# Sensing.net
KiCad netlist of a schematic drawn in Altium Designer
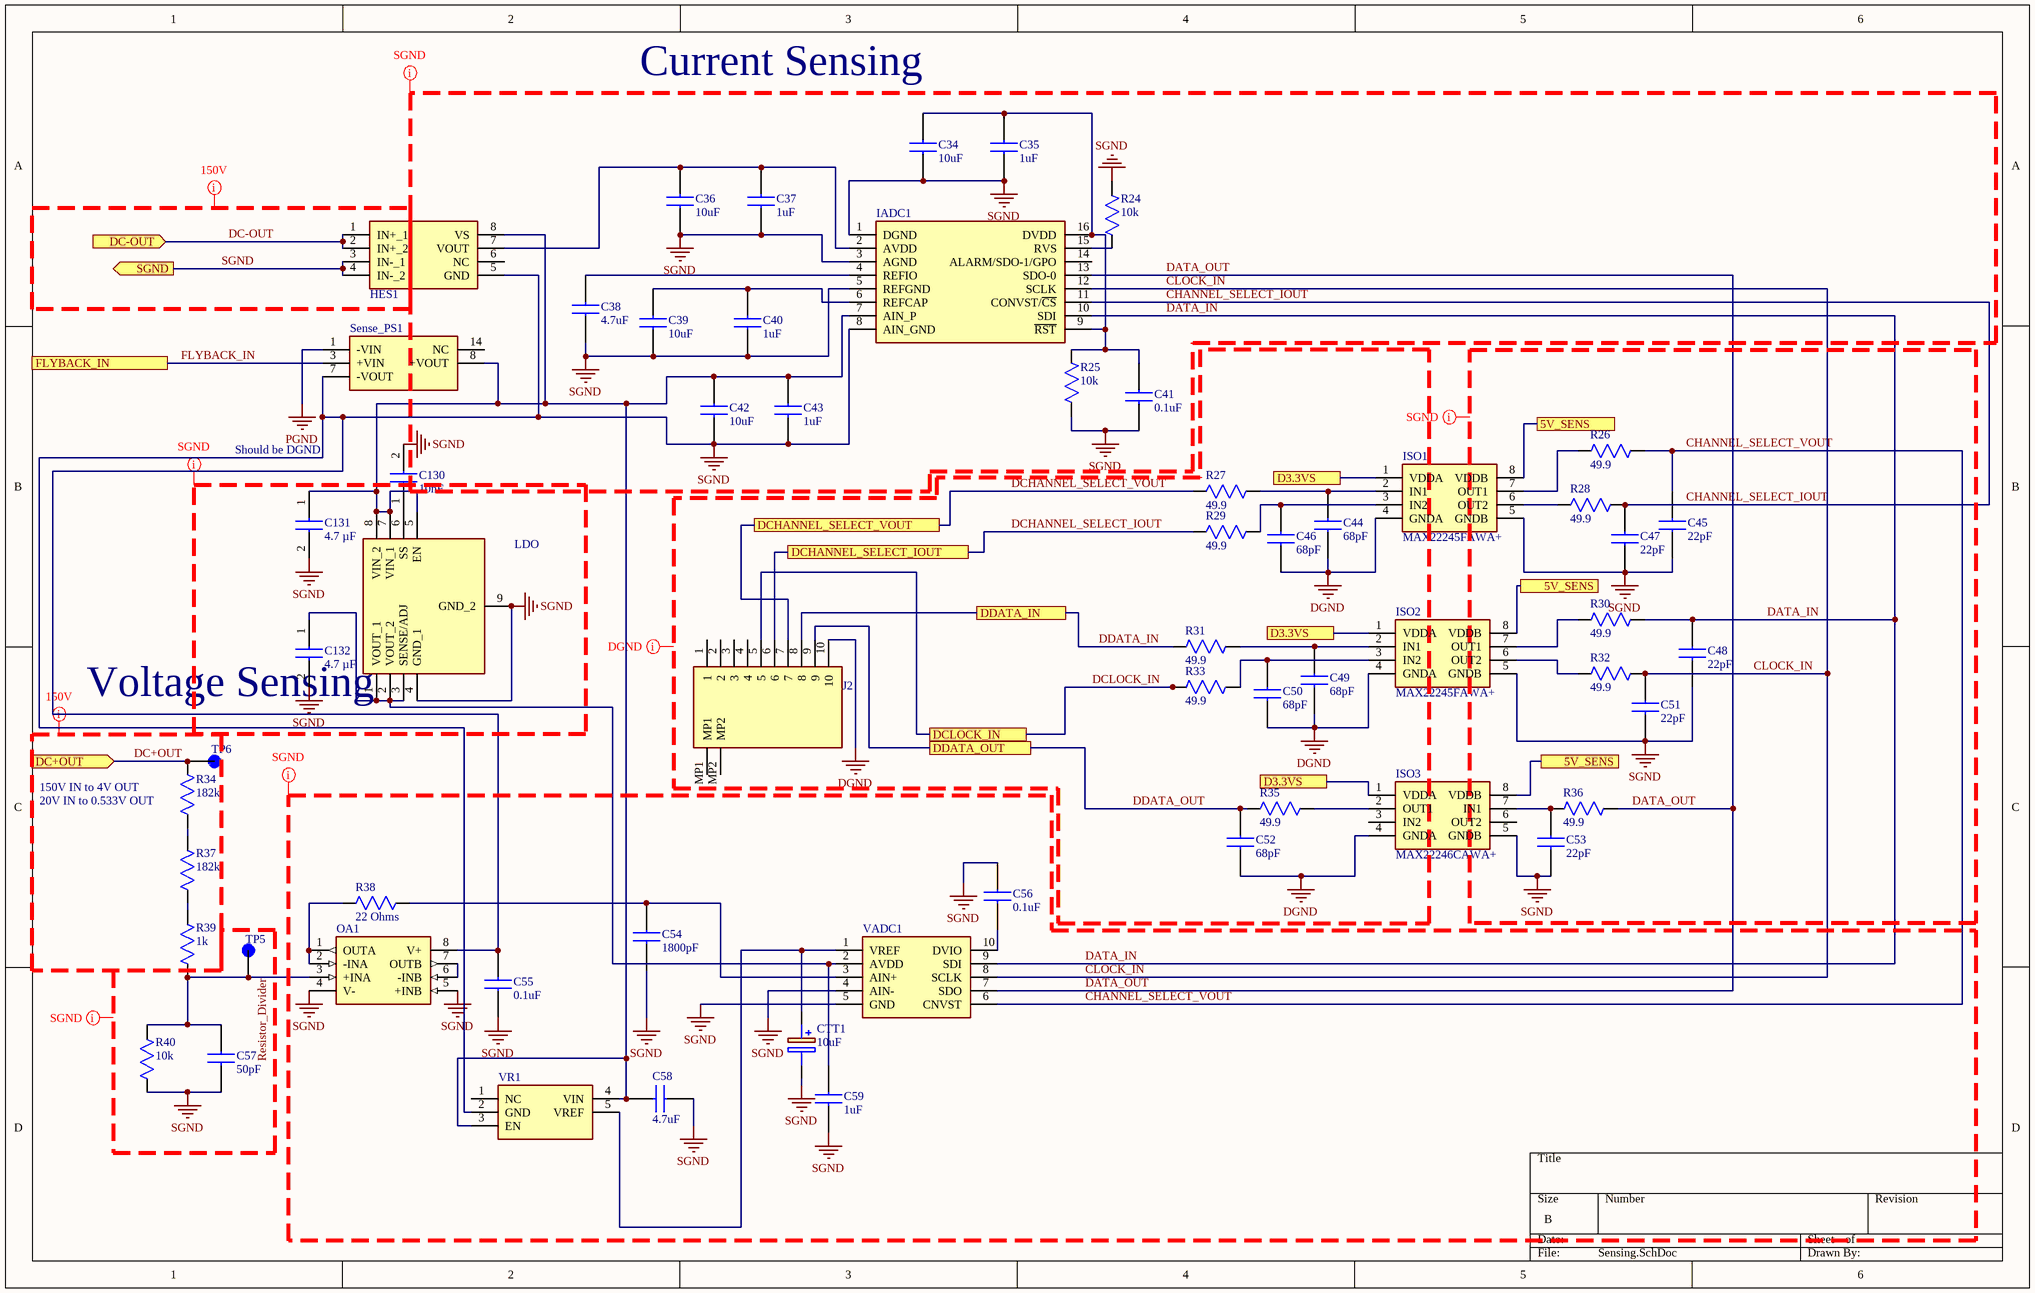
[diagram p0: Sensing.SchDoc]

(export (version "E")
  (design (tool "Eeschema 10.0.6"))
  (components
    (comp (ref "C34")
      (value "10uF")
      (footprint "CAPC2012X140N")
      (description "Capacitor")
      (fields
        (field (name "MANUFACTURER_PART_NUMBER") "CL21B106KPQNNNE")
        (field (name "MOUSER PART NUMBER") "187-CL21B106KPQNNNE")
      )
      (libsource (lib "Sensing") (part "CL21B106KPQNNNE"))
    )
    (comp (ref "C35")
      (value "1uF")
      (footprint "CAPC2012X152N")
      (description "Capacitor")
      (fields
        (field (name "MANUFACTURER_PART_NUMBER") "0805ZC105KAT2A")
        (field (name "MOUSER PART NUMBER") "581-0805ZC105K")
      )
      (libsource (lib "Sensing") (part "0805ZC105KAT2A"))
    )
    (comp (ref "C36")
      (value "10uF")
      (footprint "CAPC2012X140N")
      (description "Capacitor")
      (fields
        (field (name "MANUFACTURER_PART_NUMBER") "CL21B106KPQNNNE")
        (field (name "MOUSER PART NUMBER") "187-CL21B106KPQNNNE")
      )
      (libsource (lib "Sensing") (part "CL21B106KPQNNNE"))
    )
    (comp (ref "C37")
      (value "1uF")
      (footprint "CAPC2012X152N")
      (description "Capacitor")
      (fields
        (field (name "MANUFACTURER_PART_NUMBER") "0805ZC105KAT2A")
        (field (name "MOUSER PART NUMBER") "581-0805ZC105K")
      )
      (libsource (lib "Sensing") (part "0805ZC105KAT2A"))
    )
    (comp (ref "C38")
      (value "4.7uF")
      (footprint "CAPC2012X140N")
      (description "Capacitor")
      (fields
        (field (name "MANUFACTURER_PART_NUMBER") "GCM21BC71A475KA73L")
        (field (name "MOUSER PART NUMBER") "81-GCM21BC71A475KA3L")
      )
      (libsource (lib "Sensing") (part "GCM21BC71A475KA73L"))
    )
    (comp (ref "C39")
      (value "10uF")
      (footprint "CAPC2012X140N")
      (description "Capacitor")
      (fields
        (field (name "MANUFACTURER_PART_NUMBER") "CL21B106KPQNNNE")
        (field (name "MOUSER PART NUMBER") "187-CL21B106KPQNNNE")
      )
      (libsource (lib "Sensing") (part "CL21B106KPQNNNE"))
    )
    (comp (ref "C40")
      (value "1uF")
      (footprint "CAPC2012X152N")
      (description "Capacitor")
      (fields
        (field (name "MANUFACTURER_PART_NUMBER") "0805ZC105KAT2A")
        (field (name "MOUSER PART NUMBER") "581-0805ZC105K")
      )
      (libsource (lib "Sensing") (part "0805ZC105KAT2A"))
    )
    (comp (ref "C41")
      (value "0.1uF")
      (footprint "CAPC1608X95N")
      (description "Capacitor")
      (fields (field (name "MANUFACTURER_PART_NUMBER") "C0603C104K5RACTU7042"))
      (libsource (lib "Sensing") (part "C0603C104K5RACTU7042"))
    )
    (comp (ref "C42")
      (value "10uF")
      (footprint "CAPC2012X140N")
      (description "Capacitor")
      (fields
        (field (name "MANUFACTURER_PART_NUMBER") "CL21B106KPQNNNE")
        (field (name "MOUSER PART NUMBER") "187-CL21B106KPQNNNE")
      )
      (libsource (lib "Sensing") (part "CL21B106KPQNNNE"))
    )
    (comp (ref "C43")
      (value "1uF")
      (footprint "CAPC2012X152N")
      (description "Capacitor")
      (fields
        (field (name "MANUFACTURER_PART_NUMBER") "0805ZC105KAT2A")
        (field (name "MOUSER PART NUMBER") "581-0805ZC105K")
      )
      (libsource (lib "Sensing") (part "0805ZC105KAT2A"))
    )
    (comp (ref "C44")
      (value "68pF")
      (footprint "C0805")
      (description "CAP CER 68PF 50V C0G/NP0 0805")
      (fields
        (field (name "MANUFACTURER_PART_NUMBER") "C0805C680J5GACTU")
        (field (name "MOUSER PART NUMBER") "80-C0805C680J5G")
      )
      (libsource (lib "Sensing") (part "C0805C680J5GACTU"))
    )
    (comp (ref "C45")
      (value "22pF")
      (footprint "C0805")
      (description "CAP CER 22PF 100V C0G/NP0 0805")
      (fields
        (field (name "MANUFACTURER_PART_NUMBER") "C0805C220J1GACTU")
        (field (name "MOUSER PART NUMBER") "80-C0805C220J1G")
      )
      (libsource (lib "Sensing") (part "C0805C220J1GACTU"))
    )
    (comp (ref "C46")
      (value "68pF")
      (footprint "C0805")
      (description "CAP CER 68PF 50V C0G/NP0 0805")
      (fields
        (field (name "MANUFACTURER_PART_NUMBER") "C0805C680J5GACTU")
        (field (name "MOUSER PART NUMBER") "80-C0805C680J5G")
      )
      (libsource (lib "Sensing") (part "C0805C680J5GACTU"))
    )
    (comp (ref "C47")
      (value "22pF")
      (footprint "C0805")
      (description "CAP CER 22PF 100V C0G/NP0 0805")
      (fields
        (field (name "MANUFACTURER_PART_NUMBER") "C0805C220J1GACTU")
        (field (name "MOUSER PART NUMBER") "80-C0805C220J1G")
      )
      (libsource (lib "Sensing") (part "C0805C220J1GACTU"))
    )
    (comp (ref "C48")
      (value "22pF")
      (footprint "C0805")
      (description "CAP CER 22PF 100V C0G/NP0 0805")
      (fields
        (field (name "MANUFACTURER_PART_NUMBER") "C0805C220J1GACTU")
        (field (name "MOUSER PART NUMBER") "80-C0805C220J1G")
      )
      (libsource (lib "Sensing") (part "C0805C220J1GACTU"))
    )
    (comp (ref "C49")
      (value "68pF")
      (footprint "C0805")
      (description "CAP CER 68PF 50V C0G/NP0 0805")
      (fields
        (field (name "MANUFACTURER_PART_NUMBER") "C0805C680J5GACTU")
        (field (name "MOUSER PART NUMBER") "80-C0805C680J5G")
      )
      (libsource (lib "Sensing") (part "C0805C680J5GACTU"))
    )
    (comp (ref "C50")
      (value "68pF")
      (footprint "C0805")
      (description "CAP CER 68PF 50V C0G/NP0 0805")
      (fields
        (field (name "MANUFACTURER_PART_NUMBER") "C0805C680J5GACTU")
        (field (name "MOUSER PART NUMBER") "80-C0805C680J5G")
      )
      (libsource (lib "Sensing") (part "C0805C680J5GACTU"))
    )
    (comp (ref "C51")
      (value "22pF")
      (footprint "C0805")
      (description "CAP CER 22PF 100V C0G/NP0 0805")
      (fields
        (field (name "MANUFACTURER_PART_NUMBER") "C0805C220J1GACTU")
        (field (name "MOUSER PART NUMBER") "80-C0805C220J1G")
      )
      (libsource (lib "Sensing") (part "C0805C220J1GACTU"))
    )
    (comp (ref "C52")
      (value "68pF")
      (footprint "C0805")
      (description "CAP CER 68PF 50V C0G/NP0 0805")
      (fields
        (field (name "MANUFACTURER_PART_NUMBER") "C0805C680J5GACTU")
        (field (name "MOUSER PART NUMBER") "80-C0805C680J5G")
      )
      (libsource (lib "Sensing") (part "C0805C680J5GACTU"))
    )
    (comp (ref "C53")
      (value "22pF")
      (footprint "C0805")
      (description "CAP CER 22PF 100V C0G/NP0 0805")
      (fields
        (field (name "MANUFACTURER_PART_NUMBER") "C0805C220J1GACTU")
        (field (name "MOUSER PART NUMBER") "80-C0805C220J1G")
      )
      (libsource (lib "Sensing") (part "C0805C220J1GACTU"))
    )
    (comp (ref "C54")
      (value "1800pF")
      (footprint "CAPC2012X70N")
      (description "Capacitor")
      (fields (field (name "MANUFACTURER_PART_NUMBER") "GRM2165C2A182JA01D"))
      (libsource (lib "Sensing") (part "GRM2165C2A182JA01D"))
    )
    (comp (ref "C55")
      (value "0.1uF")
      (footprint "CAPC1608X95N")
      (description "Capacitor")
      (fields (field (name "MANUFACTURER_PART_NUMBER") "C0603C104K5RACTU7042"))
      (libsource (lib "Sensing") (part "C0603C104K5RACTU7042"))
    )
    (comp (ref "C56")
      (value "0.1uF")
      (footprint "CAPC1608X95N")
      (description "Capacitor")
      (fields (field (name "MANUFACTURER_PART_NUMBER") "C0603C104K5RACTU7042"))
      (libsource (lib "Sensing") (part "C0603C104K5RACTU7042"))
    )
    (comp (ref "C57")
      (value "50pF")
      (footprint "CAPC1608X90N")
      (description "Capacitor")
      (fields
        (field (name "MANUFACTURER_PART_NUMBER") "CC0603JRNPO9BN500")
        (field (name "MOUSER PART NUMBER") "603-CC0603JRNP9BN500")
      )
      (libsource (lib "Sensing") (part "CC0603JRNPO9BN500"))
    )
    (comp (ref "C58")
      (value "4.7uF")
      (footprint "CAPC2012X140N")
      (description "Capacitor")
      (fields
        (field (name "MANUFACTURER_PART_NUMBER") "GCM21BC71A475KA73L")
        (field (name "MOUSER PART NUMBER") "81-GCM21BC71A475KA3L")
      )
      (libsource (lib "Sensing") (part "GCM21BC71A475KA73L"))
    )
    (comp (ref "C59")
      (value "1uF")
      (footprint "CAPC2012X152N")
      (description "Capacitor")
      (fields
        (field (name "MANUFACTURER_PART_NUMBER") "0805ZC105KAT2A")
        (field (name "MOUSER PART NUMBER") "581-0805ZC105K")
      )
      (libsource (lib "Sensing") (part "0805ZC105KAT2A"))
    )
    (comp (ref "C130")
      (value "10nF")
      (footprint "CAPC2012X140N")
      (description "10000 pF ±10% 10V Ceramic Capacitor X7R 0805 (2012 Metric)")
      (fields
        (field (name "MANUFACTURER_PART_NUMBER") "885012207011")
        (field (name "MOUSER PART NUMBER") "710-885012207011")
      )
      (libsource (lib "Sensing") (part "885012207011"))
    )
    (comp (ref "C131")
      (value "4.7 µF")
      (footprint "CAPC2012X140N")
      (description "4.7 µF ±10% 10V Ceramic Capacitor X7S 0805 (2012 Metric)")
      (fields
        (field (name "MANUFACTURER_PART_NUMBER") "GCM21BC71A475KA73L")
        (field (name "MOUSER PART NUMBER") "81-GCM21BC71A475KA3L")
      )
      (libsource (lib "Sensing") (part "GCM21BC71A475KA73L_1"))
    )
    (comp (ref "C132")
      (value "4.7 µF")
      (footprint "CAPC2012X140N")
      (description "4.7 µF ±10% 10V Ceramic Capacitor X7S 0805 (2012 Metric)")
      (fields
        (field (name "MANUFACTURER_PART_NUMBER") "GCM21BC71A475KA73L")
        (field (name "MOUSER PART NUMBER") "81-GCM21BC71A475KA3L")
      )
      (libsource (lib "Sensing") (part "GCM21BC71A475KA73L_1"))
    )
    (comp (ref "CTT1")
      (value "10uF")
      (footprint "CAPPC2114X150N")
      (description "Capacitor Polarised")
      (fields
        (field (name "MANUFACTURER_PART_NUMBER") "TLCR106M020XTA")
        (field (name "MOUSER PART NUMBER") "581-TLCR106M020XTA")
      )
      (libsource (lib "Sensing") (part "TLCR106M020XTA"))
    )
    (comp (ref "HES1")
      (value "TMCS1107A3UQDR")
      (footprint "SOIC127P600X175-8N")
      (description "SENSOR CURRENT HALL EFFECT 8SOIC")
      (fields (field (name "MOUSER PART NUMBER") "595-TMCS1107A3UQDR"))
      (libsource (lib "iSense") (part "TMCS1107A3UQDR"))
    )
    (comp (ref "IADC1")
      (value "ADS8681IPWR")
      (footprint "SOP65P640X120-16N")
      (description "Integrated Circuit")
      (fields (field (name "MOUSER PART NUMBER") "595-ADS8681IPWR"))
      (libsource (lib "Sensing") (part "ADS8681IPWR"))
    )
    (comp (ref "ISO1")
      (value "MAX22245FAWA+")
      (footprint "SOIC127P1031X265-8N")
      (description "DG ISO 5KV 2CH CAN/RS232 8-SOIC")
      (libsource (lib "Control_Board") (part "MAX22245FAWA+"))
    )
    (comp (ref "ISO2")
      (value "MAX22245FAWA+")
      (footprint "SOIC127P1031X265-8N")
      (description "DG ISO 5KV 2CH CAN/RS232 8-SOIC")
      (libsource (lib "Control_Board") (part "MAX22245FAWA+"))
    )
    (comp (ref "ISO3")
      (value "MAX22246CAWA+")
      (footprint "SOIC127P1031X265-8N")
      (description "DG ISO 5KV 2CH CAN/RS232 8-SOIC")
      (fields (field (name "MOUSER PART NUMBER") "700-MAX22246CAWA+"))
      (libsource (lib "Control_Board") (part "MAX22246CAWA+"))
    )
    (comp (ref "J2")
      (value "0545501033")
      (footprint "0545501033")
      (description "CONN FFC FPC TOP 10POS 0.5MM R/A")
      (libsource (lib "Sensing") (part "0545501033"))
    )
    (comp (ref "LDO")
      (value "ADP7142ARDZ-1.8")
      (footprint "SOIC127P600X175-9N")
      (description "Integrated Circuit")
      (fields (field (name "MOUSER PART NUMBER") "584-ADP7142ARDZ-1.8"))
      (libsource (lib "Sensing") (part "ADP7142ARDZ-1.8"))
    )
    (comp (ref "OA1")
      (value "LT1498CS8#PBF")
      (footprint "SamacSys:SOIC127P599X175-8N")
      (description "Integrated Circuit")
      (fields (field (name "MOUSER PART NUMBER") "584-LT1498CS8#PBF"))
      (libsource (lib "Sensing") (part "LT1498CS8#PBF"))
    )
    (comp (ref "R24")
      (value "10k")
      (footprint "RESC2012X70N")
      (description "Resistor")
      (fields
        (field (name "MANUFACTURER_PART_NUMBER") "ERJ-PB6B1002V")
        (field (name "MOUSER PART NUMBER") "667-ERJ-PB6B1002V")
      )
      (libsource (lib "Sensing") (part "ERJ-PB6B1002V"))
    )
    (comp (ref "R25")
      (value "10k")
      (footprint "RESC2012X70N")
      (description "Resistor")
      (fields
        (field (name "MANUFACTURER_PART_NUMBER") "ERJ-PB6B1002V")
        (field (name "MOUSER PART NUMBER") "667-ERJ-PB6B1002V")
      )
      (libsource (lib "Sensing") (part "ERJ-PB6B1002V"))
    )
    (comp (ref "R26")
      (value "49.9")
      (footprint "RESC2013X84N")
      (description "RES SMD 49.9 OHM 0.1% 1W 0805")
      (fields
        (field (name "MANUFACTURER_PART_NUMBER") "PCAN0805E49R9BST5")
        (field (name "MOUSER PART NUMBER") "71-PCAN0805E49R9BST5")
      )
      (libsource (lib "Sensing") (part "PCAN0805E49R9BST5"))
    )
    (comp (ref "R27")
      (value "49.9")
      (footprint "RESC2013X84N")
      (description "RES SMD 49.9 OHM 0.1% 1W 0805")
      (fields
        (field (name "MANUFACTURER_PART_NUMBER") "PCAN0805E49R9BST5")
        (field (name "MOUSER PART NUMBER") "71-PCAN0805E49R9BST5")
      )
      (libsource (lib "Sensing") (part "PCAN0805E49R9BST5"))
    )
    (comp (ref "R28")
      (value "49.9")
      (footprint "RESC2013X84N")
      (description "RES SMD 49.9 OHM 0.1% 1W 0805")
      (fields
        (field (name "MANUFACTURER_PART_NUMBER") "PCAN0805E49R9BST5")
        (field (name "MOUSER PART NUMBER") "71-PCAN0805E49R9BST5")
      )
      (libsource (lib "Sensing") (part "PCAN0805E49R9BST5"))
    )
    (comp (ref "R29")
      (value "49.9")
      (footprint "RESC2013X84N")
      (description "RES SMD 49.9 OHM 0.1% 1W 0805")
      (fields
        (field (name "MANUFACTURER_PART_NUMBER") "PCAN0805E49R9BST5")
        (field (name "MOUSER PART NUMBER") "71-PCAN0805E49R9BST5")
      )
      (libsource (lib "Sensing") (part "PCAN0805E49R9BST5"))
    )
    (comp (ref "R30")
      (value "49.9")
      (footprint "RESC2013X84N")
      (description "RES SMD 49.9 OHM 0.1% 1W 0805")
      (fields
        (field (name "MANUFACTURER_PART_NUMBER") "PCAN0805E49R9BST5")
        (field (name "MOUSER PART NUMBER") "71-PCAN0805E49R9BST5")
      )
      (libsource (lib "Sensing") (part "PCAN0805E49R9BST5"))
    )
    (comp (ref "R31")
      (value "49.9")
      (footprint "RESC2013X84N")
      (description "RES SMD 49.9 OHM 0.1% 1W 0805")
      (fields
        (field (name "MANUFACTURER_PART_NUMBER") "PCAN0805E49R9BST5")
        (field (name "MOUSER PART NUMBER") "71-PCAN0805E49R9BST5")
      )
      (libsource (lib "Sensing") (part "PCAN0805E49R9BST5"))
    )
    (comp (ref "R32")
      (value "49.9")
      (footprint "RESC2013X84N")
      (description "RES SMD 49.9 OHM 0.1% 1W 0805")
      (fields
        (field (name "MANUFACTURER_PART_NUMBER") "PCAN0805E49R9BST5")
        (field (name "MOUSER PART NUMBER") "71-PCAN0805E49R9BST5")
      )
      (libsource (lib "Sensing") (part "PCAN0805E49R9BST5"))
    )
    (comp (ref "R33")
      (value "49.9")
      (footprint "RESC2013X84N")
      (description "RES SMD 49.9 OHM 0.1% 1W 0805")
      (fields
        (field (name "MANUFACTURER_PART_NUMBER") "PCAN0805E49R9BST5")
        (field (name "MOUSER PART NUMBER") "71-PCAN0805E49R9BST5")
      )
      (libsource (lib "Sensing") (part "PCAN0805E49R9BST5"))
    )
    (comp (ref "R34")
      (value "182k")
      (footprint "RESC3216X70N")
      (description "Resistor")
      (fields (field (name "MANUFACTURER_PART_NUMBER") "ERA-8AEB1823V"))
      (libsource (lib "Sensing") (part "ERA-8AEB1823V"))
    )
    (comp (ref "R35")
      (value "49.9")
      (footprint "RESC2013X84N")
      (description "RES SMD 49.9 OHM 0.1% 1W 0805")
      (fields
        (field (name "MANUFACTURER_PART_NUMBER") "PCAN0805E49R9BST5")
        (field (name "MOUSER PART NUMBER") "71-PCAN0805E49R9BST5")
      )
      (libsource (lib "Sensing") (part "PCAN0805E49R9BST5"))
    )
    (comp (ref "R36")
      (value "49.9")
      (footprint "RESC2013X84N")
      (description "RES SMD 49.9 OHM 0.1% 1W 0805")
      (fields
        (field (name "MANUFACTURER_PART_NUMBER") "PCAN0805E49R9BST5")
        (field (name "MOUSER PART NUMBER") "71-PCAN0805E49R9BST5")
      )
      (libsource (lib "Sensing") (part "PCAN0805E49R9BST5"))
    )
    (comp (ref "R37")
      (value "182k")
      (footprint "RESC3216X70N")
      (description "Resistor")
      (fields (field (name "MANUFACTURER_PART_NUMBER") "ERA-8AEB1823V"))
      (libsource (lib "Sensing") (part "ERA-8AEB1823V"))
    )
    (comp (ref "R38")
      (value "22 Ohms")
      (footprint "RESC2012X65N")
      (description "Resistor")
      (fields
        (field (name "MANUFACTURER_PART_NUMBER") "CPF-A-0805B22RE1")
        (field (name "MOUSER PART NUMBER") "279-CPF-A-0805B22RE1")
      )
      (libsource (lib "Sensing") (part "CPF-A-0805B22RE1"))
    )
    (comp (ref "R39")
      (value "1k")
      (footprint "RESC2012X70N")
      (description "Resistor")
      (fields
        (field (name "MANUFACTURER_PART_NUMBER") "ERJ-PB6B1001V")
        (field (name "MOUSER PART NUMBER") "667-ERJ-PB6B1001V")
      )
      (libsource (lib "Sensing") (part "ERJ-PB6B1001V"))
    )
    (comp (ref "R40")
      (value "10k")
      (footprint "RESC2012X70N")
      (description "Resistor")
      (fields
        (field (name "MANUFACTURER_PART_NUMBER") "ERJ-PB6B1002V")
        (field (name "MOUSER PART NUMBER") "667-ERJ-PB6B1002V")
      )
      (libsource (lib "Sensing") (part "ERJ-PB6B1002V"))
    )
    (comp (ref "Sense_PS1")
      (value "NXF1S0505MC-R7")
      (footprint "NXF1S0505MCR13")
      (description "Power Supply")
      (fields (field (name "MOUSER PART NUMBER") "580-NXF1S0505MC-R7"))
      (libsource (lib "Sensing") (part "NXF1S0505MC-R7"))
    )
    (comp (ref "TP5")
      (value "Voltage Divider Testpoint")
      (footprint "TP_5011")
      (description "Test Point 5011")
      (fields (field (name "MP") "altium_native_batch"))
      (libsource (lib "Sensing") (part "Test Point 5011"))
    )
    (comp (ref "TP6")
      (value "Test Point 5011")
      (footprint "TP_5011")
      (fields (field (name "MP") "altium_native_batch"))
      (libsource (lib "Sensing") (part "Test Point 5011"))
    )
    (comp (ref "VADC1")
      (value "MCP33131-10-E/MS")
      (footprint "SOP50P490X110-10N")
      (description "Integrated Circuit")
      (fields (field (name "MOUSER PART NUMBER") "579-MCP33131-10-E/MS"))
      (libsource (lib "Sensing") (part "MCP33131-10-E_MS"))
    )
    (comp (ref "VR1")
      (value "LM4132AMF-4.1_NOPB")
      (footprint "SOT95P280X145-5N")
      (description "Integrated Circuit")
      (fields
        (field (name "MANUFACTURER_PART_NUMBER") "LM4132AMF-4.1/NOPB")
        (field (name "MOUSER PART NUMBER") "926-LM4132AMF4.1NOPB")
      )
      (libsource (lib "Sensing") (part "LM4132AMF-4.1_NOPB"))
    )
  )
  (nets
    (net (code "1") (name "/5V_SENS") (class "Default")
      (node (ref "ISO1") (pin "8") (pinfunction "VDDB_8") (pintype "passive"))
      (node (ref "ISO2") (pin "8") (pinfunction "VDDB_8") (pintype "passive"))
      (node (ref "ISO3") (pin "8") (pinfunction "VDDB_8") (pintype "passive"))
    )
    (net (code "2") (name "/CHANNEL_SELECT_IOUT") (class "Default")
      (node (ref "C47") (pin "2") (pinfunction "2_2") (pintype "passive"))
      (node (ref "IADC1") (pin "11") (pinfunction "CONVST/~{CS}_11") (pintype "passive"))
      (node (ref "R28") (pin "2") (pinfunction "2_2") (pintype "passive"))
    )
    (net (code "3") (name "/CHANNEL_SELECT_VOUT") (class "Default")
      (node (ref "C45") (pin "2") (pinfunction "2_2") (pintype "passive"))
      (node (ref "R26") (pin "2") (pinfunction "2_2") (pintype "passive"))
      (node (ref "VADC1") (pin "6") (pinfunction "CNVST_6") (pintype "passive"))
    )
    (net (code "4") (name "/CLOCK_IN") (class "Default")
      (node (ref "C51") (pin "2") (pinfunction "2_2") (pintype "passive"))
      (node (ref "IADC1") (pin "12") (pinfunction "SCLK_12") (pintype "passive"))
      (node (ref "R32") (pin "2") (pinfunction "2_2") (pintype "passive"))
      (node (ref "VADC1") (pin "8") (pinfunction "SCLK_8") (pintype "passive"))
    )
    (net (code "5") (name "/D3.3VS") (class "Default")
      (node (ref "ISO1") (pin "1") (pinfunction "VDDA_1") (pintype "passive"))
      (node (ref "ISO2") (pin "1") (pinfunction "VDDA_1") (pintype "passive"))
      (node (ref "ISO3") (pin "1") (pinfunction "VDDA_1") (pintype "passive"))
    )
    (net (code "6") (name "/DATA_IN") (class "Default")
      (node (ref "C48") (pin "2") (pinfunction "2_2") (pintype "passive"))
      (node (ref "IADC1") (pin "10") (pinfunction "SDI_10") (pintype "passive"))
      (node (ref "R30") (pin "2") (pinfunction "2_2") (pintype "passive"))
      (node (ref "VADC1") (pin "9") (pinfunction "SDI_9") (pintype "passive"))
    )
    (net (code "7") (name "/DATA_OUT") (class "Default")
      (node (ref "IADC1") (pin "13") (pinfunction "SDO-0_13") (pintype "passive"))
      (node (ref "R36") (pin "2") (pinfunction "2_2") (pintype "passive"))
      (node (ref "VADC1") (pin "7") (pinfunction "SDO_7") (pintype "passive"))
    )
    (net (code "8") (name "/DC+OUT") (class "Default")
      (node (ref "R34") (pin "1") (pinfunction "1_1") (pintype "passive"))
      (node (ref "TP6") (pin "1") (pinfunction "1_1") (pintype "passive"))
    )
    (net (code "9") (name "/DC-OUT") (class "Default")
      (node (ref "HES1") (pin "1") (pinfunction "IN+_1_1") (pintype "passive"))
      (node (ref "HES1") (pin "2") (pinfunction "IN+_2_2") (pintype "passive"))
    )
    (net (code "10") (name "/DCHANNEL_SELECT_IOUT") (class "Default")
      (node (ref "J2") (pin "6") (pinfunction "6_6") (pintype "passive"))
      (node (ref "R29") (pin "1") (pinfunction "1_1") (pintype "passive"))
    )
    (net (code "11") (name "/DCHANNEL_SELECT_VOUT") (class "Default")
      (node (ref "J2") (pin "7") (pinfunction "7_7") (pintype "passive"))
      (node (ref "R27") (pin "1") (pinfunction "1_1") (pintype "passive"))
    )
    (net (code "12") (name "/DCLOCK_IN") (class "Default")
      (node (ref "J2") (pin "5") (pinfunction "5_5") (pintype "passive"))
      (node (ref "R33") (pin "1") (pinfunction "1_1") (pintype "passive"))
    )
    (net (code "13") (name "/DDATA_IN") (class "Default")
      (node (ref "J2") (pin "8") (pinfunction "8_8") (pintype "passive"))
      (node (ref "R31") (pin "1") (pinfunction "1_1") (pintype "passive"))
    )
    (net (code "14") (name "/DDATA_OUT") (class "Default")
      (node (ref "C52") (pin "2") (pinfunction "2_2") (pintype "passive"))
      (node (ref "J2") (pin "9") (pinfunction "9_9") (pintype "passive"))
      (node (ref "R35") (pin "1") (pinfunction "1_1") (pintype "passive"))
    )
    (net (code "15") (name "/FLYBACK_IN") (class "Default")
      (node (ref "Sense_PS1") (pin "3") (pinfunction "+VIN_3") (pintype "passive"))
    )
    (net (code "16") (name "/Resistor_Divider") (class "Default")
      (node (ref "C57") (pin "1") (pinfunction "1_1") (pintype "passive"))
      (node (ref "OA1") (pin "3") (pinfunction "+INA_3") (pintype "input"))
      (node (ref "R39") (pin "1") (pinfunction "1_1") (pintype "passive"))
      (node (ref "R40") (pin "2") (pinfunction "2_2") (pintype "passive"))
      (node (ref "TP5") (pin "1") (pinfunction "1_1") (pintype "passive"))
    )
    (net (code "17") (name "DGND") (class "Default")
      (node (ref "C44") (pin "1") (pinfunction "1_1") (pintype "passive"))
      (node (ref "C46") (pin "1") (pinfunction "1_1") (pintype "passive"))
      (node (ref "C49") (pin "1") (pinfunction "1_1") (pintype "passive"))
      (node (ref "C50") (pin "1") (pinfunction "1_1") (pintype "passive"))
      (node (ref "C52") (pin "1") (pinfunction "1_1") (pintype "passive"))
      (node (ref "ISO1") (pin "4") (pinfunction "GNDA_4") (pintype "passive"))
      (node (ref "ISO2") (pin "4") (pinfunction "GNDA_4") (pintype "passive"))
      (node (ref "ISO3") (pin "4") (pinfunction "GNDA_4") (pintype "passive"))
      (node (ref "J2") (pin "10") (pinfunction "10_10") (pintype "passive"))
    )
    (net (code "18") (name "Net-(CTT1-+)") (class "Default")
      (node (ref "CTT1") (pin "1") (pinfunction "+_1") (pintype "passive"))
      (node (ref "VADC1") (pin "1") (pinfunction "VREF_1") (pintype "passive"))
      (node (ref "VR1") (pin "5") (pinfunction "VREF_5") (pintype "passive"))
    )
    (net (code "19") (name "Net-(HES1-VOUT)") (class "Default")
      (node (ref "C36") (pin "2") (pinfunction "2_2") (pintype "passive"))
      (node (ref "C37") (pin "2") (pinfunction "2_2") (pintype "passive"))
      (node (ref "HES1") (pin "7") (pinfunction "VOUT_7") (pintype "passive"))
      (node (ref "IADC1") (pin "2") (pinfunction "AVDD_2") (pintype "passive"))
    )
    (net (code "20") (name "Net-(HES1-VS)") (class "Default")
      (node (ref "C131") (pin "1") (pinfunction "1_1") (pintype "passive"))
      (node (ref "C42") (pin "2") (pinfunction "2_2") (pintype "passive"))
      (node (ref "C43") (pin "2") (pinfunction "2_2") (pintype "passive"))
      (node (ref "C58") (pin "2") (pinfunction "2_2") (pintype "passive"))
      (node (ref "HES1") (pin "8") (pinfunction "VS_8") (pintype "passive"))
      (node (ref "IADC1") (pin "7") (pinfunction "AIN_P_7") (pintype "passive"))
      (node (ref "LDO") (pin "5") (pinfunction "EN_5") (pintype "passive"))
      (node (ref "LDO") (pin "7") (pinfunction "VIN_1_7") (pintype "passive"))
      (node (ref "LDO") (pin "8") (pinfunction "VIN_2_8") (pintype "passive"))
      (node (ref "Sense_PS1") (pin "8") (pinfunction "+VOUT_8") (pintype "passive"))
      (node (ref "VR1") (pin "3") (pinfunction "EN_3") (pintype "passive"))
      (node (ref "VR1") (pin "4") (pinfunction "VIN_4") (pintype "passive"))
    )
    (net (code "21") (name "Net-(IADC1-DVDD)") (class "Default")
      (node (ref "C34") (pin "2") (pinfunction "2_2") (pintype "passive"))
      (node (ref "C35") (pin "2") (pinfunction "2_2") (pintype "passive"))
      (node (ref "C41") (pin "2") (pinfunction "2_2") (pintype "passive"))
      (node (ref "IADC1") (pin "16") (pinfunction "DVDD_16") (pintype "passive"))
      (node (ref "IADC1") (pin "9") (pinfunction "~{RST}_9") (pintype "passive"))
      (node (ref "R25") (pin "1") (pinfunction "1_1") (pintype "passive"))
    )
    (net (code "22") (name "Net-(IADC1-REFCAP)") (class "Default")
      (node (ref "C39") (pin "2") (pinfunction "2_2") (pintype "passive"))
      (node (ref "C40") (pin "2") (pinfunction "2_2") (pintype "passive"))
      (node (ref "IADC1") (pin "6") (pinfunction "REFCAP_6") (pintype "passive"))
    )
    (net (code "23") (name "Net-(IADC1-REFIO)") (class "Default")
      (node (ref "C38") (pin "2") (pinfunction "2_2") (pintype "passive"))
      (node (ref "IADC1") (pin "4") (pinfunction "REFIO_4") (pintype "passive"))
    )
    (net (code "24") (name "Net-(IADC1-RVS)") (class "Default")
      (node (ref "IADC1") (pin "15") (pinfunction "RVS_15") (pintype "passive"))
      (node (ref "R24") (pin "1") (pinfunction "1_1") (pintype "passive"))
    )
    (net (code "25") (name "Net-(ISO1-IN1)") (class "Default")
      (node (ref "C44") (pin "2") (pinfunction "2_2") (pintype "passive"))
      (node (ref "ISO1") (pin "2") (pinfunction "IN1_2") (pintype "passive"))
      (node (ref "R27") (pin "2") (pinfunction "2_2") (pintype "passive"))
    )
    (net (code "26") (name "Net-(ISO1-IN2)") (class "Default")
      (node (ref "C46") (pin "2") (pinfunction "2_2") (pintype "passive"))
      (node (ref "ISO1") (pin "3") (pinfunction "IN2_3") (pintype "passive"))
      (node (ref "R29") (pin "2") (pinfunction "2_2") (pintype "passive"))
    )
    (net (code "27") (name "Net-(ISO1-OUT1)") (class "Default")
      (node (ref "ISO1") (pin "7") (pinfunction "OUT1_7") (pintype "passive"))
      (node (ref "R26") (pin "1") (pinfunction "1_1") (pintype "passive"))
    )
    (net (code "28") (name "Net-(ISO1-OUT2)") (class "Default")
      (node (ref "ISO1") (pin "6") (pinfunction "OUT2_6") (pintype "passive"))
      (node (ref "R28") (pin "1") (pinfunction "1_1") (pintype "passive"))
    )
    (net (code "29") (name "Net-(ISO2-IN1)") (class "Default")
      (node (ref "C49") (pin "2") (pinfunction "2_2") (pintype "passive"))
      (node (ref "ISO2") (pin "2") (pinfunction "IN1_2") (pintype "passive"))
      (node (ref "R31") (pin "2") (pinfunction "2_2") (pintype "passive"))
    )
    (net (code "30") (name "Net-(ISO2-IN2)") (class "Default")
      (node (ref "C50") (pin "2") (pinfunction "2_2") (pintype "passive"))
      (node (ref "ISO2") (pin "3") (pinfunction "IN2_3") (pintype "passive"))
      (node (ref "R33") (pin "2") (pinfunction "2_2") (pintype "passive"))
    )
    (net (code "31") (name "Net-(ISO2-OUT1)") (class "Default")
      (node (ref "ISO2") (pin "7") (pinfunction "OUT1_7") (pintype "passive"))
      (node (ref "R30") (pin "1") (pinfunction "1_1") (pintype "passive"))
    )
    (net (code "32") (name "Net-(ISO2-OUT2)") (class "Default")
      (node (ref "ISO2") (pin "6") (pinfunction "OUT2_6") (pintype "passive"))
      (node (ref "R32") (pin "1") (pinfunction "1_1") (pintype "passive"))
    )
    (net (code "33") (name "Net-(ISO3-IN1)") (class "Default")
      (node (ref "C53") (pin "2") (pinfunction "2_2") (pintype "passive"))
      (node (ref "ISO3") (pin "7") (pinfunction "IN1_7") (pintype "passive"))
      (node (ref "R36") (pin "1") (pinfunction "1_1") (pintype "passive"))
    )
    (net (code "34") (name "Net-(ISO3-OUT1)") (class "Default")
      (node (ref "ISO3") (pin "2") (pinfunction "OUT1_2") (pintype "passive"))
      (node (ref "R35") (pin "2") (pinfunction "2_2") (pintype "passive"))
    )
    (net (code "35") (name "Net-(LDO-SENSE{slash}ADJ)") (class "Default")
      (node (ref "C132") (pin "1") (pinfunction "1_1") (pintype "passive"))
      (node (ref "C59") (pin "2") (pinfunction "2_2") (pintype "passive"))
      (node (ref "LDO") (pin "1") (pinfunction "VOUT_1_1") (pintype "passive"))
      (node (ref "LDO") (pin "2") (pinfunction "VOUT_2_2") (pintype "passive"))
      (node (ref "LDO") (pin "3") (pinfunction "SENSE/ADJ_3") (pintype "passive"))
      (node (ref "VADC1") (pin "2") (pinfunction "AVDD_2") (pintype "passive"))
    )
    (net (code "36") (name "Net-(LDO-SS)") (class "Default")
      (node (ref "C130") (pin "1") (pinfunction "1_1") (pintype "passive"))
      (node (ref "LDO") (pin "6") (pinfunction "SS_6") (pintype "passive"))
    )
    (net (code "37") (name "Net-(OA1--INA)") (class "Default")
      (node (ref "OA1") (pin "1") (pinfunction "OUTA_1") (pintype "output"))
      (node (ref "OA1") (pin "2") (pinfunction "-INA_2") (pintype "input"))
      (node (ref "R38") (pin "1") (pinfunction "1_1") (pintype "passive"))
    )
    (net (code "38") (name "Net-(OA1--INB)") (class "Default")
      (node (ref "OA1") (pin "6") (pinfunction "-INB_6") (pintype "input"))
      (node (ref "OA1") (pin "7") (pinfunction "OUTB_7") (pintype "output"))
    )
    (net (code "39") (name "Net-(R34-Pad2)") (class "Default")
      (node (ref "R34") (pin "2") (pinfunction "2_2") (pintype "passive"))
      (node (ref "R37") (pin "2") (pinfunction "2_2") (pintype "passive"))
    )
    (net (code "40") (name "Net-(R37-Pad1)") (class "Default")
      (node (ref "R37") (pin "1") (pinfunction "1_1") (pintype "passive"))
      (node (ref "R39") (pin "2") (pinfunction "2_2") (pintype "passive"))
    )
    (net (code "41") (name "Net-(VADC1-AIN+)") (class "Default")
      (node (ref "C54") (pin "1") (pinfunction "1_1") (pintype "passive"))
      (node (ref "R38") (pin "2") (pinfunction "2_2") (pintype "passive"))
      (node (ref "VADC1") (pin "3") (pinfunction "AIN+_3") (pintype "passive"))
    )
    (net (code "42") (name "Net-(VADC1-DVIO)") (class "Default")
      (node (ref "C56") (pin "1") (pinfunction "1_1") (pintype "passive"))
      (node (ref "VADC1") (pin "10") (pinfunction "DVIO_10") (pintype "passive"))
    )
    (net (code "43") (name "PGND") (class "Default")
      (node (ref "Sense_PS1") (pin "1") (pinfunction "-VIN_1") (pintype "passive"))
    )
    (net (code "44") (name "SGND") (class "Default")
      (node (ref "C130") (pin "2") (pinfunction "2_2") (pintype "passive"))
      (node (ref "C131") (pin "2") (pinfunction "2_2") (pintype "passive"))
      (node (ref "C132") (pin "2") (pinfunction "2_2") (pintype "passive"))
      (node (ref "C34") (pin "1") (pinfunction "1_1") (pintype "passive"))
      (node (ref "C35") (pin "1") (pinfunction "1_1") (pintype "passive"))
      (node (ref "C36") (pin "1") (pinfunction "1_1") (pintype "passive"))
      (node (ref "C37") (pin "1") (pinfunction "1_1") (pintype "passive"))
      (node (ref "C38") (pin "1") (pinfunction "1_1") (pintype "passive"))
      (node (ref "C39") (pin "1") (pinfunction "1_1") (pintype "passive"))
      (node (ref "C40") (pin "1") (pinfunction "1_1") (pintype "passive"))
      (node (ref "C41") (pin "1") (pinfunction "1_1") (pintype "passive"))
      (node (ref "C42") (pin "1") (pinfunction "1_1") (pintype "passive"))
      (node (ref "C43") (pin "1") (pinfunction "1_1") (pintype "passive"))
      (node (ref "C45") (pin "1") (pinfunction "1_1") (pintype "passive"))
      (node (ref "C47") (pin "1") (pinfunction "1_1") (pintype "passive"))
      (node (ref "C48") (pin "1") (pinfunction "1_1") (pintype "passive"))
      (node (ref "C51") (pin "1") (pinfunction "1_1") (pintype "passive"))
      (node (ref "C53") (pin "1") (pinfunction "1_1") (pintype "passive"))
      (node (ref "C54") (pin "2") (pinfunction "2_2") (pintype "passive"))
      (node (ref "C55") (pin "1") (pinfunction "1_1") (pintype "passive"))
      (node (ref "C55") (pin "2") (pinfunction "2_2") (pintype "passive"))
      (node (ref "C56") (pin "2") (pinfunction "2_2") (pintype "passive"))
      (node (ref "C57") (pin "2") (pinfunction "2_2") (pintype "passive"))
      (node (ref "C58") (pin "1") (pinfunction "1_1") (pintype "passive"))
      (node (ref "C59") (pin "1") (pinfunction "1_1") (pintype "passive"))
      (node (ref "CTT1") (pin "2") (pinfunction "-_2") (pintype "passive"))
      (node (ref "HES1") (pin "3") (pinfunction "IN-_1_3") (pintype "passive"))
      (node (ref "HES1") (pin "4") (pinfunction "IN-_2_4") (pintype "passive"))
      (node (ref "HES1") (pin "5") (pinfunction "GND_5") (pintype "passive"))
      (node (ref "IADC1") (pin "1") (pinfunction "DGND_1") (pintype "passive"))
      (node (ref "IADC1") (pin "3") (pinfunction "AGND_3") (pintype "passive"))
      (node (ref "IADC1") (pin "5") (pinfunction "REFGND_5") (pintype "passive"))
      (node (ref "IADC1") (pin "8") (pinfunction "AIN_GND_8") (pintype "passive"))
      (node (ref "ISO1") (pin "5") (pinfunction "GNDB_5") (pintype "passive"))
      (node (ref "ISO2") (pin "5") (pinfunction "GNDB_5") (pintype "passive"))
      (node (ref "ISO3") (pin "5") (pinfunction "GNDB_5") (pintype "passive"))
      (node (ref "LDO") (pin "4") (pinfunction "GND_1_4") (pintype "passive"))
      (node (ref "LDO") (pin "9") (pinfunction "GND_2_9") (pintype "passive"))
      (node (ref "OA1") (pin "4") (pinfunction "V-_4") (pintype "passive"))
      (node (ref "OA1") (pin "5") (pinfunction "+INB_5") (pintype "input"))
      (node (ref "OA1") (pin "8") (pinfunction "V+_8") (pintype "passive"))
      (node (ref "R24") (pin "2") (pinfunction "2_2") (pintype "passive"))
      (node (ref "R25") (pin "2") (pinfunction "2_2") (pintype "passive"))
      (node (ref "R40") (pin "1") (pinfunction "1_1") (pintype "passive"))
      (node (ref "Sense_PS1") (pin "7") (pinfunction "-VOUT_7") (pintype "passive"))
      (node (ref "VADC1") (pin "4") (pinfunction "AIN-_4") (pintype "passive"))
      (node (ref "VADC1") (pin "5") (pinfunction "GND_5") (pintype "power_in"))
      (node (ref "VR1") (pin "2") (pinfunction "GND_2") (pintype "passive"))
    )
    (net (code "45") (name "unconnected-(HES1-NC-Pad6)") (class "Default")
      (node (ref "HES1") (pin "6") (pinfunction "NC_6") (pintype "passive"))
    )
    (net (code "46") (name "unconnected-(IADC1-ALARM{slash}SDO-1{slash}GPO-Pad14)") (class "Default")
      (node (ref "IADC1") (pin "14") (pinfunction "ALARM/SDO-1/GPO_14") (pintype "passive"))
    )
    (net (code "47") (name "unconnected-(ISO3-IN2-Pad3)") (class "Default")
      (node (ref "ISO3") (pin "3") (pinfunction "IN2_3") (pintype "passive"))
    )
    (net (code "48") (name "unconnected-(ISO3-OUT2-Pad6)") (class "Default")
      (node (ref "ISO3") (pin "6") (pinfunction "OUT2_6") (pintype "passive"))
    )
    (net (code "49") (name "unconnected-(J2-Pad1)") (class "Default")
      (node (ref "J2") (pin "1") (pinfunction "1_1") (pintype "passive"))
    )
    (net (code "50") (name "unconnected-(J2-Pad2)") (class "Default")
      (node (ref "J2") (pin "2") (pinfunction "2_2") (pintype "passive"))
    )
    (net (code "51") (name "unconnected-(J2-Pad3)") (class "Default")
      (node (ref "J2") (pin "3") (pinfunction "3_3") (pintype "passive"))
    )
    (net (code "52") (name "unconnected-(J2-Pad4)") (class "Default")
      (node (ref "J2") (pin "4") (pinfunction "4_4") (pintype "passive"))
    )
    (net (code "53") (name "unconnected-(J2-PadMP1)") (class "Default")
      (node (ref "J2") (pin "MP1") (pinfunction "MP1_MP1") (pintype "passive"))
    )
    (net (code "54") (name "unconnected-(J2-PadMP2)") (class "Default")
      (node (ref "J2") (pin "MP2") (pinfunction "MP2_MP2") (pintype "passive"))
    )
    (net (code "55") (name "unconnected-(Sense_PS1-NC-Pad14)") (class "Default")
      (node (ref "Sense_PS1") (pin "14") (pinfunction "NC_14") (pintype "passive"))
    )
    (net (code "56") (name "unconnected-(VR1-NC-Pad1)") (class "Default")
      (node (ref "VR1") (pin "1") (pinfunction "NC_1") (pintype "passive"))
    )
  )
)
